# LDOTEST.net
KiCad netlist of a schematic drawn in Altium Designer
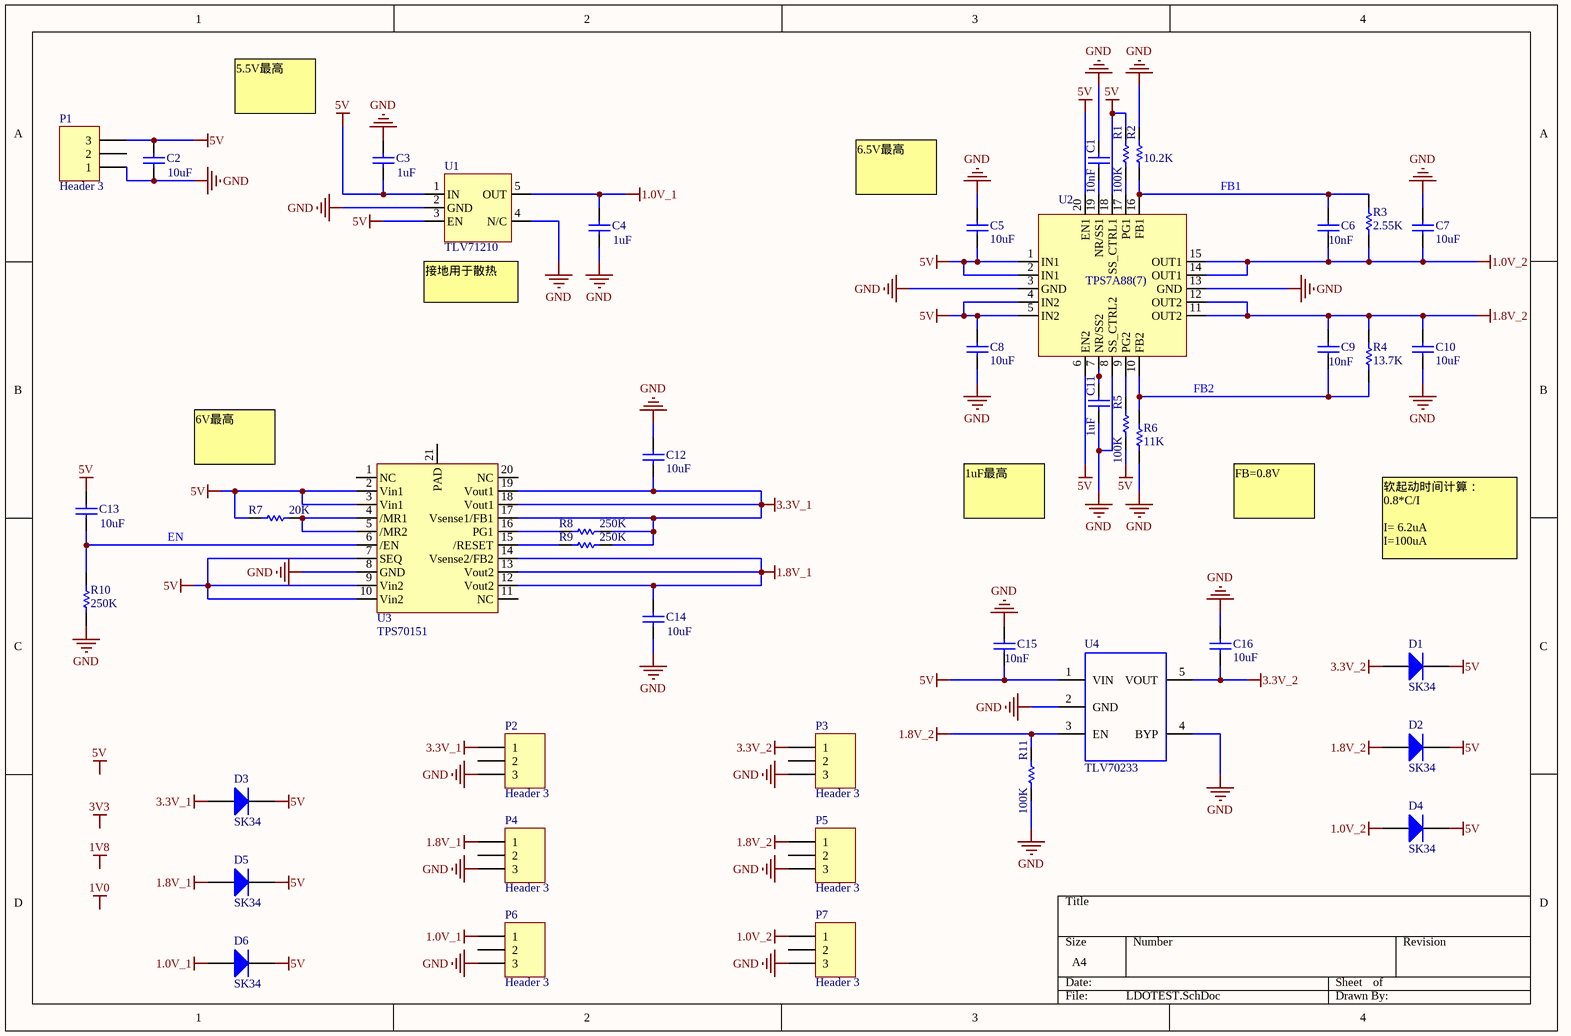
[diagram p0: LDOTEST.SchDoc]

(export (version "E")
  (design (tool "Eeschema 10.0.6"))
  (components
    (comp (ref "C1")
      (value "10nF")
      (footprint "C2012")
      (description "贴片电容")
      (fields (field (name "Comment") "Cap") (field (name "PUBLISHER") "Altium Limited"))
      (libsource (lib "Sparks") (part "Cap"))
    )
    (comp (ref "C2")
      (value "10uF")
      (footprint "C2012")
      (description "贴片电容")
      (fields (field (name "Comment") "Cap") (field (name "PUBLISHER") "Altium Limited"))
      (libsource (lib "Sparks") (part "Cap"))
    )
    (comp (ref "C3")
      (value "1uF")
      (footprint "C2012")
      (description "贴片电容")
      (fields (field (name "Comment") "Cap") (field (name "PUBLISHER") "Altium Limited"))
      (libsource (lib "Sparks") (part "Cap"))
    )
    (comp (ref "C4")
      (value "1uF")
      (footprint "C2012")
      (description "贴片电容")
      (fields (field (name "Comment") "Cap") (field (name "PUBLISHER") "Altium Limited"))
      (libsource (lib "Sparks") (part "Cap"))
    )
    (comp (ref "C5")
      (value "10uF")
      (footprint "C2012")
      (description "贴片电容")
      (fields (field (name "Comment") "Cap") (field (name "PUBLISHER") "Altium Limited"))
      (libsource (lib "Sparks") (part "Cap"))
    )
    (comp (ref "C6")
      (value "10nF")
      (footprint "C2012")
      (description "贴片电容")
      (fields (field (name "Comment") "Cap") (field (name "PUBLISHER") "Altium Limited"))
      (libsource (lib "Sparks") (part "Cap"))
    )
    (comp (ref "C7")
      (value "10uF")
      (footprint "C2012")
      (description "贴片电容")
      (fields (field (name "Comment") "Cap") (field (name "PUBLISHER") "Altium Limited"))
      (libsource (lib "Sparks") (part "Cap"))
    )
    (comp (ref "C8")
      (value "10uF")
      (footprint "C2012")
      (description "贴片电容")
      (fields (field (name "Comment") "Cap") (field (name "PUBLISHER") "Altium Limited"))
      (libsource (lib "Sparks") (part "Cap"))
    )
    (comp (ref "C9")
      (value "10nF")
      (footprint "C2012")
      (description "贴片电容")
      (fields (field (name "Comment") "Cap") (field (name "PUBLISHER") "Altium Limited"))
      (libsource (lib "Sparks") (part "Cap"))
    )
    (comp (ref "C10")
      (value "10uF")
      (footprint "C2012")
      (description "贴片电容")
      (fields (field (name "Comment") "Cap") (field (name "PUBLISHER") "Altium Limited"))
      (libsource (lib "Sparks") (part "Cap"))
    )
    (comp (ref "C11")
      (value "1uF")
      (footprint "C2012")
      (description "贴片电容")
      (fields (field (name "Comment") "Cap") (field (name "PUBLISHER") "Altium Limited"))
      (libsource (lib "Sparks") (part "Cap"))
    )
    (comp (ref "C12")
      (value "10uF")
      (footprint "C2012")
      (description "贴片电容")
      (fields (field (name "Comment") "Cap") (field (name "PUBLISHER") "Altium Limited"))
      (libsource (lib "Sparks") (part "Cap"))
    )
    (comp (ref "C13")
      (value "10uF")
      (footprint "C2012")
      (description "贴片电容")
      (fields (field (name "Comment") "Cap") (field (name "PUBLISHER") "Altium Limited"))
      (libsource (lib "Sparks") (part "Cap"))
    )
    (comp (ref "C14")
      (value "10uF")
      (footprint "C2012")
      (description "贴片电容")
      (fields (field (name "Comment") "Cap") (field (name "PUBLISHER") "Altium Limited"))
      (libsource (lib "Sparks") (part "Cap"))
    )
    (comp (ref "C15")
      (value "10nF")
      (footprint "C2012")
      (description "贴片电容")
      (fields (field (name "Comment") "Cap") (field (name "PUBLISHER") "Altium Limited"))
      (libsource (lib "Sparks") (part "Cap"))
    )
    (comp (ref "C16")
      (value "10uF")
      (footprint "C2012")
      (description "贴片电容")
      (fields (field (name "Comment") "Cap") (field (name "PUBLISHER") "Altium Limited"))
      (libsource (lib "Sparks") (part "Cap"))
    )
    (comp (ref "D1")
      (value "SK34")
      (footprint "1206")
      (description "High Conductance Fast Diode")
      (fields (field (name "PUBLISHER") "Altium Limited"))
      (libsource (lib "K60-V4.0") (part "Diode 1N4148"))
    )
    (comp (ref "D2")
      (value "SK34")
      (footprint "1206")
      (description "High Conductance Fast Diode")
      (fields (field (name "PUBLISHER") "Altium Limited"))
      (libsource (lib "K60-V4.0") (part "Diode 1N4148"))
    )
    (comp (ref "D3")
      (value "SK34")
      (footprint "1206")
      (description "High Conductance Fast Diode")
      (fields (field (name "PUBLISHER") "Altium Limited"))
      (libsource (lib "K60-V4.0") (part "Diode 1N4148"))
    )
    (comp (ref "D4")
      (value "SK34")
      (footprint "1206")
      (description "High Conductance Fast Diode")
      (fields (field (name "PUBLISHER") "Altium Limited"))
      (libsource (lib "K60-V4.0") (part "Diode 1N4148"))
    )
    (comp (ref "D5")
      (value "SK34")
      (footprint "1206")
      (description "High Conductance Fast Diode")
      (fields (field (name "PUBLISHER") "Altium Limited"))
      (libsource (lib "K60-V4.0") (part "Diode 1N4148"))
    )
    (comp (ref "D6")
      (value "SK34")
      (footprint "1206")
      (description "High Conductance Fast Diode")
      (fields (field (name "PUBLISHER") "Altium Limited"))
      (libsource (lib "K60-V4.0") (part "Diode 1N4148"))
    )
    (comp (ref "P1")
      (value "Header 3")
      (footprint "HDR1X3")
      (description "Header, 3-Pin")
      (fields (field (name "PUBLISHER") "Altium Limited"))
      (libsource (lib "") (part "Header 3_1"))
    )
    (comp (ref "P2")
      (value "Header 3")
      (footprint "HDR1X3")
      (description "Header, 3-Pin")
      (fields (field (name "PUBLISHER") "Altium Limited"))
      (libsource (lib "Sparks") (part "Header 3"))
    )
    (comp (ref "P3")
      (value "Header 3")
      (footprint "HDR1X3")
      (description "Header, 3-Pin")
      (fields (field (name "PUBLISHER") "Altium Limited"))
      (libsource (lib "Sparks") (part "Header 3"))
    )
    (comp (ref "P4")
      (value "Header 3")
      (footprint "HDR1X3")
      (description "Header, 3-Pin")
      (fields (field (name "PUBLISHER") "Altium Limited"))
      (libsource (lib "Sparks") (part "Header 3"))
    )
    (comp (ref "P5")
      (value "Header 3")
      (footprint "HDR1X3")
      (description "Header, 3-Pin")
      (fields (field (name "PUBLISHER") "Altium Limited"))
      (libsource (lib "Sparks") (part "Header 3"))
    )
    (comp (ref "P6")
      (value "Header 3")
      (footprint "HDR1X3")
      (description "Header, 3-Pin")
      (fields (field (name "PUBLISHER") "Altium Limited"))
      (libsource (lib "Sparks") (part "Header 3"))
    )
    (comp (ref "P7")
      (value "Header 3")
      (footprint "HDR1X3")
      (description "Header, 3-Pin")
      (fields (field (name "PUBLISHER") "Altium Limited"))
      (libsource (lib "Sparks") (part "Header 3"))
    )
    (comp (ref "R1")
      (value "100K")
      (footprint "R2012")
      (description "贴片电阻")
      (fields (field (name "Comment") "Res") (field (name "PUBLISHER") "Altium Limited"))
      (libsource (lib "Sparks") (part "Res"))
    )
    (comp (ref "R2")
      (value "10.2K")
      (footprint "R2012")
      (description "贴片电阻")
      (fields (field (name "Comment") "Res") (field (name "PUBLISHER") "Altium Limited"))
      (libsource (lib "Sparks") (part "Res"))
    )
    (comp (ref "R3")
      (value "2.55K")
      (footprint "R2012")
      (description "贴片电阻")
      (fields (field (name "Comment") "Res") (field (name "PUBLISHER") "Altium Limited"))
      (libsource (lib "Sparks") (part "Res"))
    )
    (comp (ref "R4")
      (value "13.7K")
      (footprint "R2012")
      (description "贴片电阻")
      (fields (field (name "Comment") "Res") (field (name "PUBLISHER") "Altium Limited"))
      (libsource (lib "Sparks") (part "Res"))
    )
    (comp (ref "R5")
      (value "100K")
      (footprint "R2012")
      (description "贴片电阻")
      (fields (field (name "Comment") "Res") (field (name "PUBLISHER") "Altium Limited"))
      (libsource (lib "Sparks") (part "Res"))
    )
    (comp (ref "R6")
      (value "11K")
      (footprint "R2012")
      (description "贴片电阻")
      (fields (field (name "Comment") "Res") (field (name "PUBLISHER") "Altium Limited"))
      (libsource (lib "Sparks") (part "Res"))
    )
    (comp (ref "R7")
      (value "20K")
      (footprint "R2012")
      (description "贴片电阻")
      (fields (field (name "Comment") "Res") (field (name "PUBLISHER") "Altium Limited"))
      (libsource (lib "Sparks") (part "Res"))
    )
    (comp (ref "R8")
      (value "250K")
      (footprint "R2012")
      (description "贴片电阻")
      (fields (field (name "Comment") "Res") (field (name "PUBLISHER") "Altium Limited"))
      (libsource (lib "Sparks") (part "Res"))
    )
    (comp (ref "R9")
      (value "250K")
      (footprint "R2012")
      (description "贴片电阻")
      (fields (field (name "Comment") "Res") (field (name "PUBLISHER") "Altium Limited"))
      (libsource (lib "Sparks") (part "Res"))
    )
    (comp (ref "R10")
      (value "250K")
      (footprint "R2012")
      (description "贴片电阻")
      (fields (field (name "Comment") "Res") (field (name "PUBLISHER") "Altium Limited"))
      (libsource (lib "Sparks") (part "Res"))
    )
    (comp (ref "R11")
      (value "100K")
      (footprint "R2012")
      (description "贴片电阻")
      (fields (field (name "Comment") "Res") (field (name "PUBLISHER") "Altium Limited"))
      (libsource (lib "Sparks") (part "Res"))
    )
    (comp (ref "U1") (value "TLV71210") (footprint "TLV712") (libsource (lib "Schlib1") (part "TLV712")))
    (comp (ref "U2")
      (value "TPS7A88(7)")
      (footprint "TPS7A88(7)")
      (libsource (lib "Schlib1") (part "TPS7A88(7)"))
    )
    (comp (ref "U3") (value "TPS70151") (footprint "TPS701") (libsource (lib "Schlib1") (part "TPS701")))
    (comp (ref "U4")
      (value "TLV70233")
      (footprint "SOT-23-5")
      (description "LDO")
      (libsource (lib "K60-V4.0") (part "MIC5219"))
    )
  )
  (nets
    (net (code "1") (name "/EN") (class "Default")
      (node (ref "C13") (pin "2") (pinfunction "2_2") (pintype "passive"))
      (node (ref "R10") (pin "1") (pinfunction "1_1") (pintype "passive"))
      (node (ref "U3") (pin "6") (pinfunction "/EN_6") (pintype "passive"))
    )
    (net (code "2") (name "/FB1") (class "Default")
      (node (ref "C6") (pin "1") (pinfunction "1_1") (pintype "passive"))
      (node (ref "R2") (pin "2") (pinfunction "2_2") (pintype "passive"))
      (node (ref "R3") (pin "1") (pinfunction "1_1") (pintype "passive"))
      (node (ref "U2") (pin "16") (pinfunction "FB1_16") (pintype "passive"))
    )
    (net (code "3") (name "/FB2") (class "Default")
      (node (ref "C9") (pin "2") (pinfunction "2_2") (pintype "passive"))
      (node (ref "R4") (pin "2") (pinfunction "2_2") (pintype "passive"))
      (node (ref "R6") (pin "1") (pinfunction "1_1") (pintype "passive"))
      (node (ref "U2") (pin "10") (pinfunction "FB2_10") (pintype "passive"))
    )
    (net (code "4") (name "1.0V_1") (class "Default")
      (node (ref "C4") (pin "1") (pinfunction "1_1") (pintype "passive"))
      (node (ref "D6") (pin "1") (pinfunction "A_1") (pintype "passive"))
      (node (ref "P6") (pin "1") (pinfunction "1_1") (pintype "passive"))
      (node (ref "U1") (pin "5") (pinfunction "OUT_5") (pintype "passive"))
    )
    (net (code "5") (name "1.0V_2") (class "Default")
      (node (ref "C6") (pin "2") (pinfunction "2_2") (pintype "passive"))
      (node (ref "C7") (pin "1") (pinfunction "1_1") (pintype "passive"))
      (node (ref "D4") (pin "1") (pinfunction "A_1") (pintype "passive"))
      (node (ref "P7") (pin "1") (pinfunction "1_1") (pintype "passive"))
      (node (ref "R3") (pin "2") (pinfunction "2_2") (pintype "passive"))
      (node (ref "U2") (pin "14") (pinfunction "OUT1_14") (pintype "passive"))
      (node (ref "U2") (pin "15") (pinfunction "OUT1_15") (pintype "passive"))
    )
    (net (code "6") (name "1.8V_1") (class "Default")
      (node (ref "C14") (pin "1") (pinfunction "1_1") (pintype "passive"))
      (node (ref "D5") (pin "1") (pinfunction "A_1") (pintype "passive"))
      (node (ref "P4") (pin "1") (pinfunction "1_1") (pintype "passive"))
      (node (ref "U3") (pin "12") (pinfunction "Vout2_12") (pintype "passive"))
      (node (ref "U3") (pin "13") (pinfunction "Vout2_13") (pintype "passive"))
      (node (ref "U3") (pin "14") (pinfunction "Vsense2/FB2_14") (pintype "passive"))
    )
    (net (code "7") (name "1.8V_2") (class "Default")
      (node (ref "C10") (pin "1") (pinfunction "1_1") (pintype "passive"))
      (node (ref "C9") (pin "1") (pinfunction "1_1") (pintype "passive"))
      (node (ref "D2") (pin "1") (pinfunction "A_1") (pintype "passive"))
      (node (ref "P5") (pin "1") (pinfunction "1_1") (pintype "passive"))
      (node (ref "R11") (pin "1") (pinfunction "1_1") (pintype "passive"))
      (node (ref "R4") (pin "1") (pinfunction "1_1") (pintype "passive"))
      (node (ref "U2") (pin "11") (pinfunction "OUT2_11") (pintype "passive"))
      (node (ref "U2") (pin "12") (pinfunction "OUT2_12") (pintype "passive"))
      (node (ref "U4") (pin "3") (pinfunction "EN_3") (pintype "passive"))
    )
    (net (code "10") (name "3.3V_1") (class "Default")
      (node (ref "C12") (pin "1") (pinfunction "1_1") (pintype "passive"))
      (node (ref "D3") (pin "1") (pinfunction "A_1") (pintype "passive"))
      (node (ref "P2") (pin "1") (pinfunction "1_1") (pintype "passive"))
      (node (ref "R8") (pin "1") (pinfunction "1_1") (pintype "passive"))
      (node (ref "R9") (pin "1") (pinfunction "1_1") (pintype "passive"))
      (node (ref "U3") (pin "17") (pinfunction "Vsense1/FB1_17") (pintype "passive"))
      (node (ref "U3") (pin "18") (pinfunction "Vout1_18") (pintype "passive"))
      (node (ref "U3") (pin "19") (pinfunction "Vout1_19") (pintype "passive"))
    )
    (net (code "11") (name "3.3V_2") (class "Default")
      (node (ref "C16") (pin "1") (pinfunction "1_1") (pintype "passive"))
      (node (ref "D1") (pin "1") (pinfunction "A_1") (pintype "passive"))
      (node (ref "P3") (pin "1") (pinfunction "1_1") (pintype "passive"))
      (node (ref "U4") (pin "5") (pinfunction "VOUT_5") (pintype "passive"))
    )
    (net (code "13") (name "5V") (class "Default")
      (node (ref "C13") (pin "1") (pinfunction "1_1") (pintype "passive"))
      (node (ref "C15") (pin "2") (pinfunction "2_2") (pintype "passive"))
      (node (ref "C2") (pin "1") (pinfunction "1_1") (pintype "passive"))
      (node (ref "C3") (pin "2") (pinfunction "2_2") (pintype "passive"))
      (node (ref "C5") (pin "1") (pinfunction "1_1") (pintype "passive"))
      (node (ref "C8") (pin "1") (pinfunction "1_1") (pintype "passive"))
      (node (ref "D1") (pin "2") (pinfunction "K_2") (pintype "passive"))
      (node (ref "D2") (pin "2") (pinfunction "K_2") (pintype "passive"))
      (node (ref "D3") (pin "2") (pinfunction "K_2") (pintype "passive"))
      (node (ref "D4") (pin "2") (pinfunction "K_2") (pintype "passive"))
      (node (ref "D5") (pin "2") (pinfunction "K_2") (pintype "passive"))
      (node (ref "D6") (pin "2") (pinfunction "K_2") (pintype "passive"))
      (node (ref "P1") (pin "3") (pinfunction "3_3") (pintype "passive"))
      (node (ref "R1") (pin "1") (pinfunction "1_1") (pintype "passive"))
      (node (ref "R5") (pin "2") (pinfunction "2_2") (pintype "passive"))
      (node (ref "R7") (pin "2") (pinfunction "2_2") (pintype "passive"))
      (node (ref "U1") (pin "1") (pinfunction "IN_1") (pintype "passive"))
      (node (ref "U1") (pin "3") (pinfunction "EN_3") (pintype "passive"))
      (node (ref "U2") (pin "1") (pinfunction "IN1_1") (pintype "passive"))
      (node (ref "U2") (pin "18") (pinfunction "SS_CTRL1_18") (pintype "passive"))
      (node (ref "U2") (pin "2") (pinfunction "IN1_2") (pintype "passive"))
      (node (ref "U2") (pin "20") (pinfunction "EN1_20") (pintype "passive"))
      (node (ref "U2") (pin "4") (pinfunction "IN2_4") (pintype "passive"))
      (node (ref "U2") (pin "5") (pinfunction "IN2_5") (pintype "passive"))
      (node (ref "U2") (pin "6") (pinfunction "EN2_6") (pintype "passive"))
      (node (ref "U3") (pin "10") (pinfunction "Vin2_10") (pintype "passive"))
      (node (ref "U3") (pin "2") (pinfunction "Vin1_2") (pintype "passive"))
      (node (ref "U3") (pin "3") (pinfunction "Vin1_3") (pintype "passive"))
      (node (ref "U3") (pin "7") (pinfunction "SEQ_7") (pintype "passive"))
      (node (ref "U3") (pin "9") (pinfunction "Vin2_9") (pintype "passive"))
      (node (ref "U4") (pin "1") (pinfunction "VIN_1") (pintype "passive"))
    )
    (net (code "14") (name "GND") (class "Default")
      (node (ref "C1") (pin "2") (pinfunction "2_2") (pintype "passive"))
      (node (ref "C10") (pin "2") (pinfunction "2_2") (pintype "passive"))
      (node (ref "C11") (pin "2") (pinfunction "2_2") (pintype "passive"))
      (node (ref "C12") (pin "2") (pinfunction "2_2") (pintype "passive"))
      (node (ref "C14") (pin "2") (pinfunction "2_2") (pintype "passive"))
      (node (ref "C15") (pin "1") (pinfunction "1_1") (pintype "passive"))
      (node (ref "C16") (pin "2") (pinfunction "2_2") (pintype "passive"))
      (node (ref "C2") (pin "2") (pinfunction "2_2") (pintype "passive"))
      (node (ref "C3") (pin "1") (pinfunction "1_1") (pintype "passive"))
      (node (ref "C4") (pin "2") (pinfunction "2_2") (pintype "passive"))
      (node (ref "C5") (pin "2") (pinfunction "2_2") (pintype "passive"))
      (node (ref "C7") (pin "2") (pinfunction "2_2") (pintype "passive"))
      (node (ref "C8") (pin "2") (pinfunction "2_2") (pintype "passive"))
      (node (ref "P1") (pin "1") (pinfunction "1_1") (pintype "passive"))
      (node (ref "P2") (pin "3") (pinfunction "3_3") (pintype "passive"))
      (node (ref "P3") (pin "3") (pinfunction "3_3") (pintype "passive"))
      (node (ref "P4") (pin "3") (pinfunction "3_3") (pintype "passive"))
      (node (ref "P5") (pin "3") (pinfunction "3_3") (pintype "passive"))
      (node (ref "P6") (pin "3") (pinfunction "3_3") (pintype "passive"))
      (node (ref "P7") (pin "3") (pinfunction "3_3") (pintype "passive"))
      (node (ref "R10") (pin "2") (pinfunction "2_2") (pintype "passive"))
      (node (ref "R11") (pin "2") (pinfunction "2_2") (pintype "passive"))
      (node (ref "R2") (pin "1") (pinfunction "1_1") (pintype "passive"))
      (node (ref "R6") (pin "2") (pinfunction "2_2") (pintype "passive"))
      (node (ref "U1") (pin "2") (pinfunction "GND_2") (pintype "passive"))
      (node (ref "U1") (pin "4") (pinfunction "N/C_4") (pintype "passive"))
      (node (ref "U2") (pin "13") (pinfunction "GND_13") (pintype "passive"))
      (node (ref "U2") (pin "3") (pinfunction "GND_3") (pintype "passive"))
      (node (ref "U2") (pin "8") (pinfunction "SS_CTRL2_8") (pintype "passive"))
      (node (ref "U3") (pin "8") (pinfunction "GND_8") (pintype "passive"))
      (node (ref "U4") (pin "2") (pinfunction "GND_2") (pintype "passive"))
      (node (ref "U4") (pin "4") (pinfunction "BYP_4") (pintype "passive"))
    )
    (net (code "15") (name "Net-(U2-NR{slash}SS1)") (class "Default")
      (node (ref "C1") (pin "1") (pinfunction "1_1") (pintype "passive"))
      (node (ref "U2") (pin "19") (pinfunction "NR/SS1_19") (pintype "passive"))
    )
    (net (code "16") (name "Net-(U2-NR{slash}SS2)") (class "Default")
      (node (ref "C11") (pin "1") (pinfunction "1_1") (pintype "passive"))
      (node (ref "U2") (pin "7") (pinfunction "NR/SS2_7") (pintype "passive"))
    )
    (net (code "17") (name "Net-(U2-PG1)") (class "Default")
      (node (ref "R1") (pin "2") (pinfunction "2_2") (pintype "passive"))
      (node (ref "U2") (pin "17") (pinfunction "PG1_17") (pintype "passive"))
    )
    (net (code "18") (name "Net-(U2-PG2)") (class "Default")
      (node (ref "R5") (pin "1") (pinfunction "1_1") (pintype "passive"))
      (node (ref "U2") (pin "9") (pinfunction "PG2_9") (pintype "passive"))
    )
    (net (code "19") (name "Net-(U3-PG1)") (class "Default")
      (node (ref "R8") (pin "2") (pinfunction "2_2") (pintype "passive"))
      (node (ref "U3") (pin "16") (pinfunction "PG1_16") (pintype "passive"))
    )
    (net (code "20") (name "Net-(U3-{slash}MR1)") (class "Default")
      (node (ref "R7") (pin "1") (pinfunction "1_1") (pintype "passive"))
      (node (ref "U3") (pin "4") (pinfunction "/MR1_4") (pintype "passive"))
      (node (ref "U3") (pin "5") (pinfunction "/MR2_5") (pintype "passive"))
    )
    (net (code "21") (name "Net-(U3-{slash}RESET)") (class "Default")
      (node (ref "R9") (pin "2") (pinfunction "2_2") (pintype "passive"))
      (node (ref "U3") (pin "15") (pinfunction "/RESET_15") (pintype "passive"))
    )
    (net (code "22") (name "unconnected-(P1-Pad2)") (class "Default")
      (node (ref "P1") (pin "2") (pinfunction "2_2") (pintype "passive"))
    )
    (net (code "23") (name "unconnected-(P2-Pad2)") (class "Default")
      (node (ref "P2") (pin "2") (pinfunction "2_2") (pintype "passive"))
    )
    (net (code "24") (name "unconnected-(P3-Pad2)") (class "Default")
      (node (ref "P3") (pin "2") (pinfunction "2_2") (pintype "passive"))
    )
    (net (code "25") (name "unconnected-(P4-Pad2)") (class "Default")
      (node (ref "P4") (pin "2") (pinfunction "2_2") (pintype "passive"))
    )
    (net (code "26") (name "unconnected-(P5-Pad2)") (class "Default")
      (node (ref "P5") (pin "2") (pinfunction "2_2") (pintype "passive"))
    )
    (net (code "27") (name "unconnected-(P6-Pad2)") (class "Default")
      (node (ref "P6") (pin "2") (pinfunction "2_2") (pintype "passive"))
    )
    (net (code "28") (name "unconnected-(P7-Pad2)") (class "Default")
      (node (ref "P7") (pin "2") (pinfunction "2_2") (pintype "passive"))
    )
    (net (code "29") (name "unconnected-(U3-NC-Pad1)") (class "Default")
      (node (ref "U3") (pin "1") (pinfunction "NC_1") (pintype "passive"))
    )
    (net (code "30") (name "unconnected-(U3-NC-Pad11)") (class "Default")
      (node (ref "U3") (pin "11") (pinfunction "NC_11") (pintype "passive"))
    )
    (net (code "31") (name "unconnected-(U3-NC-Pad20)") (class "Default")
      (node (ref "U3") (pin "20") (pinfunction "NC_20") (pintype "passive"))
    )
    (net (code "32") (name "unconnected-(U3-PAD-Pad21)") (class "Default")
      (node (ref "U3") (pin "21") (pinfunction "PAD_21") (pintype "passive"))
    )
  )
)
